# atmega.net
KiCad netlist of a schematic drawn in EAGLE
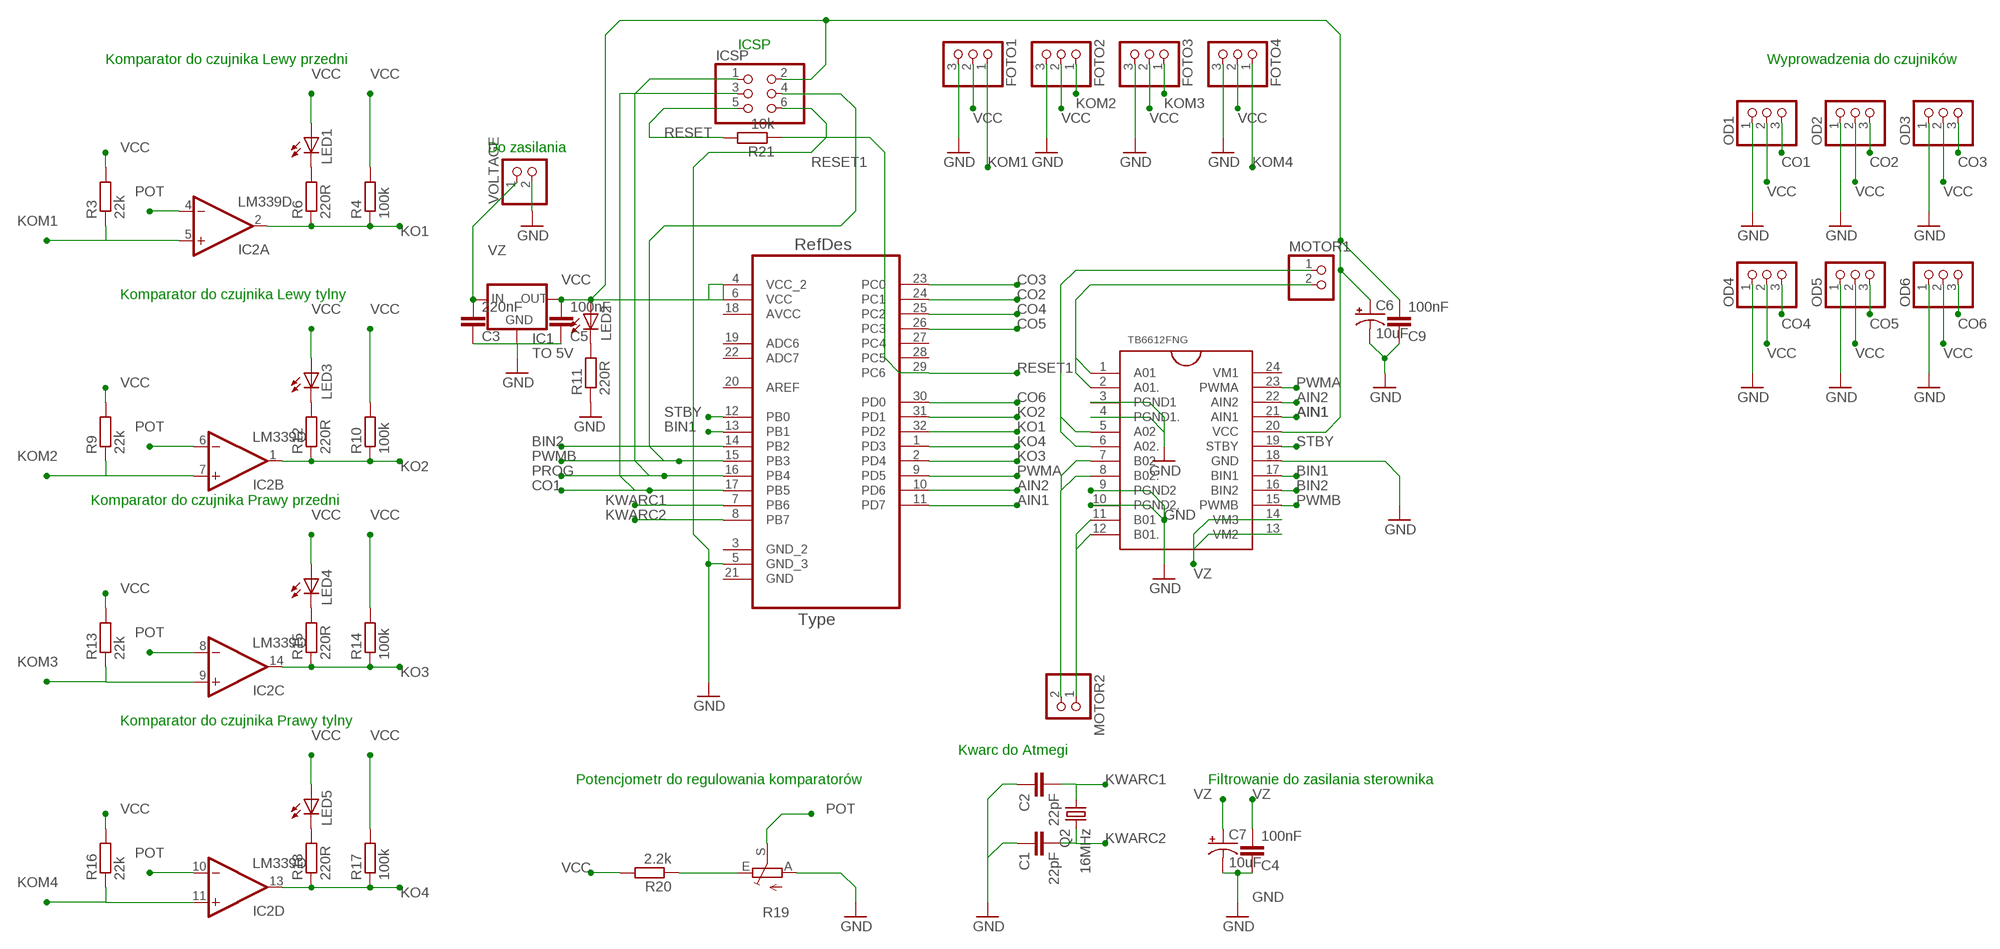
[diagram p0: schematic, sheet 1]

(export (version "E")
  (design (tool "Eeschema 10.0.6"))
  (components
    (comp (ref "C1")
      (value "22pF")
      (footprint "eagle-import:C0805")
      (fields (field (name "SPICEPREFIX") "C"))
      (libsource (lib "eagle-import") (part "C-EUC0805"))
    )
    (comp (ref "C2")
      (value "22pF")
      (footprint "eagle-import:C0805")
      (libsource (lib "eagle-import") (part "C-EUC0805"))
    )
    (comp (ref "C3")
      (value "220nF")
      (footprint "eagle-import:C0805")
      (fields (field (name "SPICEPREFIX") "C"))
      (libsource (lib "eagle-import") (part "C-EUC0805"))
    )
    (comp (ref "C4")
      (value "100nF")
      (footprint "eagle-import:C0805")
      (fields (field (name "SPICEPREFIX") "C"))
      (libsource (lib "eagle-import") (part "C-EUC0805"))
    )
    (comp (ref "C5")
      (value "100nF")
      (footprint "eagle-import:C0805")
      (fields (field (name "SPICEPREFIX") "C"))
      (libsource (lib "eagle-import") (part "C-EUC0805"))
    )
    (comp (ref "C6")
      (value "10uF")
      (footprint "eagle-import:PANASONIC_C")
      (libsource (lib "eagle-import") (part "22UF-POLAR-PANASONIC_C-35V-20%"))
    )
    (comp (ref "C7")
      (value "10uF")
      (footprint "eagle-import:PANASONIC_C")
      (libsource (lib "eagle-import") (part "22UF-POLAR-PANASONIC_C-35V-20%"))
    )
    (comp (ref "C9")
      (value "100nF")
      (footprint "eagle-import:C0805")
      (fields (field (name "SPICEPREFIX") "C"))
      (libsource (lib "eagle-import") (part "C-EUC0805"))
    )
    (comp (ref "FOTO1")
      (value "PINHD-1X3")
      (footprint "eagle-import:1X03")
      (libsource (lib "eagle-import") (part "PINHD-1X3"))
    )
    (comp (ref "FOTO2")
      (value "PINHD-1X3")
      (footprint "eagle-import:1X03")
      (libsource (lib "eagle-import") (part "PINHD-1X3"))
    )
    (comp (ref "FOTO3")
      (value "PINHD-1X3")
      (footprint "eagle-import:1X03")
      (libsource (lib "eagle-import") (part "PINHD-1X3"))
    )
    (comp (ref "FOTO4")
      (value "PINHD-1X3")
      (footprint "eagle-import:1X03")
      (libsource (lib "eagle-import") (part "PINHD-1X3"))
    )
    (comp (ref "IC1")
      (value "TO 5V")
      (footprint "eagle-import:TO220V")
      (libsource (lib "eagle-import") (part "LM1117T--V5.0"))
    )
    (comp (ref "IC2")
      (value "LM339D")
      (footprint "eagle-import:SO14")
      (libsource (lib "eagle-import") (part "LM339D"))
    )
    (comp (ref "ICSP")
      (value "PINHD-2X3")
      (footprint "eagle-import:2X03")
      (libsource (lib "eagle-import") (part "PINHD-2X3"))
    )
    (comp (ref "LED1")
      (value "LEDCHIPLED_0805")
      (footprint "eagle-import:CHIPLED_0805")
      (libsource (lib "eagle-import") (part "LEDCHIPLED_0805"))
    )
    (comp (ref "LED2")
      (value "LEDCHIPLED_0805")
      (footprint "eagle-import:CHIPLED_0805")
      (libsource (lib "eagle-import") (part "LEDCHIPLED_0805"))
    )
    (comp (ref "LED3")
      (value "LEDCHIPLED_0805")
      (footprint "eagle-import:CHIPLED_0805")
      (libsource (lib "eagle-import") (part "LEDCHIPLED_0805"))
    )
    (comp (ref "LED4")
      (value "LEDCHIPLED_0805")
      (footprint "eagle-import:CHIPLED_0805")
      (libsource (lib "eagle-import") (part "LEDCHIPLED_0805"))
    )
    (comp (ref "LED5")
      (value "LEDCHIPLED_0805")
      (footprint "eagle-import:CHIPLED_0805")
      (libsource (lib "eagle-import") (part "LEDCHIPLED_0805"))
    )
    (comp (ref "MOTOR1")
      (value "PINHD-1X2")
      (footprint "eagle-import:1X02")
      (libsource (lib "eagle-import") (part "PINHD-1X2"))
    )
    (comp (ref "MOTOR2")
      (value "PINHD-1X2")
      (footprint "eagle-import:1X02")
      (libsource (lib "eagle-import") (part "PINHD-1X2"))
    )
    (comp (ref "OD1")
      (value "PINHD-1X3")
      (footprint "eagle-import:1X03")
      (libsource (lib "eagle-import") (part "PINHD-1X3"))
    )
    (comp (ref "OD2")
      (value "PINHD-1X3")
      (footprint "eagle-import:1X03")
      (libsource (lib "eagle-import") (part "PINHD-1X3"))
    )
    (comp (ref "OD3")
      (value "PINHD-1X3")
      (footprint "eagle-import:1X03")
      (libsource (lib "eagle-import") (part "PINHD-1X3"))
    )
    (comp (ref "OD4")
      (value "PINHD-1X3")
      (footprint "eagle-import:1X03")
      (libsource (lib "eagle-import") (part "PINHD-1X3"))
    )
    (comp (ref "OD5")
      (value "PINHD-1X3")
      (footprint "eagle-import:1X03")
      (libsource (lib "eagle-import") (part "PINHD-1X3"))
    )
    (comp (ref "OD6")
      (value "PINHD-1X3")
      (footprint "eagle-import:1X03")
      (libsource (lib "eagle-import") (part "PINHD-1X3"))
    )
    (comp (ref "Q2")
      (value "16MHz")
      (footprint "eagle-import:CSM-7X-DU")
      (libsource (lib "eagle-import") (part "CSM-7X-DU"))
    )
    (comp (ref "R3")
      (value "22k")
      (footprint "eagle-import:M0805")
      (libsource (lib "eagle-import") (part "R-EU_M0805"))
    )
    (comp (ref "R4")
      (value "100k")
      (footprint "eagle-import:M0805")
      (libsource (lib "eagle-import") (part "R-EU_M0805"))
    )
    (comp (ref "R6")
      (value "220R")
      (footprint "eagle-import:M0805")
      (libsource (lib "eagle-import") (part "R-EU_M0805"))
    )
    (comp (ref "R9")
      (value "22k")
      (footprint "eagle-import:M0805")
      (libsource (lib "eagle-import") (part "R-EU_M0805"))
    )
    (comp (ref "R10")
      (value "100k")
      (footprint "eagle-import:M0805")
      (libsource (lib "eagle-import") (part "R-EU_M0805"))
    )
    (comp (ref "R11")
      (value "220R")
      (footprint "eagle-import:M0805")
      (libsource (lib "eagle-import") (part "R-EU_M0805"))
    )
    (comp (ref "R12")
      (value "220R")
      (footprint "eagle-import:M0805")
      (libsource (lib "eagle-import") (part "R-EU_M0805"))
    )
    (comp (ref "R13")
      (value "22k")
      (footprint "eagle-import:M0805")
      (libsource (lib "eagle-import") (part "R-EU_M0805"))
    )
    (comp (ref "R14")
      (value "100k")
      (footprint "eagle-import:M0805")
      (libsource (lib "eagle-import") (part "R-EU_M0805"))
    )
    (comp (ref "R15")
      (value "220R")
      (footprint "eagle-import:M0805")
      (libsource (lib "eagle-import") (part "R-EU_M0805"))
    )
    (comp (ref "R16")
      (value "22k")
      (footprint "eagle-import:M0805")
      (libsource (lib "eagle-import") (part "R-EU_M0805"))
    )
    (comp (ref "R17")
      (value "100k")
      (footprint "eagle-import:M0805")
      (libsource (lib "eagle-import") (part "R-EU_M0805"))
    )
    (comp (ref "R18")
      (value "220R")
      (footprint "eagle-import:M0805")
      (libsource (lib "eagle-import") (part "R-EU_M0805"))
    )
    (comp (ref "R19")
      (value "TRIM_EU-B25P")
      (footprint "eagle-import:B25P")
      (libsource (lib "eagle-import") (part "TRIM_EU-B25P"))
    )
    (comp (ref "R20")
      (value "2.2k")
      (footprint "eagle-import:M0805")
      (libsource (lib "eagle-import") (part "R-EU_M0805"))
    )
    (comp (ref "R21")
      (value "10k")
      (footprint "eagle-import:M0805")
      (libsource (lib "eagle-import") (part "R-EU_M0805"))
    )
    (comp (ref "U$1")
      (value "TB6612FNG")
      (footprint "eagle-import:SSOP24")
      (libsource (lib "eagle-import") (part "TB6612FNG"))
    )
    (comp (ref "U1")
      (value "ATMEGA328P-AU")
      (footprint "eagle-import:QFP80P900X900X120-32N")
      (libsource (lib "eagle-import") (part "ATMEGA328P-AU"))
    )
    (comp (ref "VOLTAGE")
      (value "PINHD-1X2")
      (footprint "eagle-import:1X02")
      (libsource (lib "eagle-import") (part "PINHD-1X2"))
    )
  )
  (nets
    (net (code "1") (name "/AIN1") (class "Default")
      (node (ref "U$1") (pin "21") (pinfunction "AIN1_21") (pintype "bidirectional"))
      (node (ref "U1") (pin "11") (pinfunction "PD7_11") (pintype "bidirectional"))
    )
    (net (code "2") (name "/AIN2") (class "Default")
      (node (ref "U$1") (pin "22") (pinfunction "AIN2_22") (pintype "bidirectional"))
      (node (ref "U1") (pin "10") (pinfunction "PD6_10") (pintype "bidirectional"))
    )
    (net (code "3") (name "/AVCC") (class "Default")
      (node (ref "U1") (pin "18") (pinfunction "AVCC_18") (pintype "power_in"))
    )
    (net (code "4") (name "/BIN1") (class "Default")
      (node (ref "U$1") (pin "17") (pinfunction "BIN1_17") (pintype "bidirectional"))
      (node (ref "U1") (pin "13") (pinfunction "PB1_13") (pintype "bidirectional"))
    )
    (net (code "5") (name "/BIN2") (class "Default")
      (node (ref "U$1") (pin "16") (pinfunction "BIN2_16") (pintype "bidirectional"))
      (node (ref "U1") (pin "14") (pinfunction "PB2_14") (pintype "bidirectional"))
    )
    (net (code "6") (name "/CO1") (class "Default")
      (node (ref "ICSP") (pin "3") (pinfunction "3_3") (pintype "passive"))
      (node (ref "OD1") (pin "3") (pinfunction "3_3") (pintype "passive"))
      (node (ref "U1") (pin "17") (pinfunction "PB5_17") (pintype "bidirectional"))
    )
    (net (code "7") (name "/CO2") (class "Default")
      (node (ref "OD2") (pin "3") (pinfunction "3_3") (pintype "passive"))
      (node (ref "U1") (pin "24") (pinfunction "PC1_24") (pintype "bidirectional"))
    )
    (net (code "8") (name "/CO3") (class "Default")
      (node (ref "OD3") (pin "3") (pinfunction "3_3") (pintype "passive"))
      (node (ref "U1") (pin "23") (pinfunction "PC0_23") (pintype "bidirectional"))
    )
    (net (code "9") (name "/CO4") (class "Default")
      (node (ref "OD4") (pin "3") (pinfunction "3_3") (pintype "passive"))
      (node (ref "U1") (pin "25") (pinfunction "PC2_25") (pintype "bidirectional"))
    )
    (net (code "10") (name "/CO5") (class "Default")
      (node (ref "OD5") (pin "3") (pinfunction "3_3") (pintype "passive"))
      (node (ref "U1") (pin "26") (pinfunction "PC3_26") (pintype "bidirectional"))
    )
    (net (code "11") (name "/CO6") (class "Default")
      (node (ref "OD6") (pin "3") (pinfunction "3_3") (pintype "passive"))
      (node (ref "U1") (pin "30") (pinfunction "PD0_30") (pintype "bidirectional"))
    )
    (net (code "12") (name "/KO1") (class "Default")
      (node (ref "IC2") (pin "2") (pinfunction "OUT_2") (pintype "open_collector"))
      (node (ref "R4") (pin "1") (pinfunction "1_1") (pintype "passive"))
      (node (ref "R6") (pin "1") (pinfunction "1_1") (pintype "passive"))
      (node (ref "U1") (pin "32") (pinfunction "PD2_32") (pintype "bidirectional"))
    )
    (net (code "13") (name "/KO2") (class "Default")
      (node (ref "IC2") (pin "1") (pinfunction "OUT_1") (pintype "open_collector"))
      (node (ref "R10") (pin "1") (pinfunction "1_1") (pintype "passive"))
      (node (ref "R12") (pin "1") (pinfunction "1_1") (pintype "passive"))
      (node (ref "U1") (pin "31") (pinfunction "PD1_31") (pintype "bidirectional"))
    )
    (net (code "14") (name "/KO3") (class "Default")
      (node (ref "IC2") (pin "14") (pinfunction "OUT_14") (pintype "open_collector"))
      (node (ref "R14") (pin "1") (pinfunction "1_1") (pintype "passive"))
      (node (ref "R15") (pin "1") (pinfunction "1_1") (pintype "passive"))
      (node (ref "U1") (pin "2") (pinfunction "PD4_2") (pintype "bidirectional"))
    )
    (net (code "15") (name "/KO4") (class "Default")
      (node (ref "IC2") (pin "13") (pinfunction "OUT_13") (pintype "open_collector"))
      (node (ref "R17") (pin "1") (pinfunction "1_1") (pintype "passive"))
      (node (ref "R18") (pin "1") (pinfunction "1_1") (pintype "passive"))
      (node (ref "U1") (pin "1") (pinfunction "PD3_1") (pintype "bidirectional"))
    )
    (net (code "16") (name "/KOM1") (class "Default")
      (node (ref "FOTO1") (pin "1") (pinfunction "1_1") (pintype "passive"))
      (node (ref "IC2") (pin "5") (pinfunction "+IN_5") (pintype "input"))
      (node (ref "R3") (pin "1") (pinfunction "1_1") (pintype "passive"))
    )
    (net (code "17") (name "/KOM2") (class "Default")
      (node (ref "FOTO2") (pin "1") (pinfunction "1_1") (pintype "passive"))
      (node (ref "IC2") (pin "7") (pinfunction "+IN_7") (pintype "input"))
      (node (ref "R9") (pin "1") (pinfunction "1_1") (pintype "passive"))
    )
    (net (code "18") (name "/KOM3") (class "Default")
      (node (ref "FOTO3") (pin "1") (pinfunction "1_1") (pintype "passive"))
      (node (ref "IC2") (pin "9") (pinfunction "+IN_9") (pintype "input"))
      (node (ref "R13") (pin "1") (pinfunction "1_1") (pintype "passive"))
    )
    (net (code "19") (name "/KOM4") (class "Default")
      (node (ref "FOTO4") (pin "1") (pinfunction "1_1") (pintype "passive"))
      (node (ref "IC2") (pin "11") (pinfunction "+IN_11") (pintype "input"))
      (node (ref "R16") (pin "1") (pinfunction "1_1") (pintype "passive"))
    )
    (net (code "20") (name "/KWARC1") (class "Default")
      (node (ref "C2") (pin "2") (pinfunction "2_2") (pintype "passive"))
      (node (ref "Q2") (pin "1") (pinfunction "1_1") (pintype "passive"))
      (node (ref "U1") (pin "7") (pinfunction "PB6_7") (pintype "bidirectional"))
    )
    (net (code "21") (name "/KWARC2") (class "Default")
      (node (ref "C1") (pin "2") (pinfunction "2_2") (pintype "passive"))
      (node (ref "Q2") (pin "2") (pinfunction "2_2") (pintype "passive"))
      (node (ref "U1") (pin "8") (pinfunction "PB7_8") (pintype "bidirectional"))
    )
    (net (code "22") (name "/POT") (class "Default")
      (node (ref "IC2") (pin "10") (pinfunction "-IN_10") (pintype "input"))
      (node (ref "IC2") (pin "4") (pinfunction "-IN_4") (pintype "input"))
      (node (ref "IC2") (pin "6") (pinfunction "-IN_6") (pintype "input"))
      (node (ref "IC2") (pin "8") (pinfunction "-IN_8") (pintype "input"))
      (node (ref "R19") (pin "S") (pinfunction "S_S") (pintype "passive"))
    )
    (net (code "23") (name "/PROG") (class "Default")
      (node (ref "ICSP") (pin "1") (pinfunction "1_1") (pintype "passive"))
      (node (ref "U1") (pin "16") (pinfunction "PB4_16") (pintype "bidirectional"))
    )
    (net (code "24") (name "/PWMA") (class "Default")
      (node (ref "U$1") (pin "23") (pinfunction "PWMA_23") (pintype "bidirectional"))
      (node (ref "U1") (pin "9") (pinfunction "PD5_9") (pintype "bidirectional"))
    )
    (net (code "25") (name "/PWMB") (class "Default")
      (node (ref "ICSP") (pin "4") (pinfunction "4_4") (pintype "passive"))
      (node (ref "U$1") (pin "15") (pinfunction "PWMB_15") (pintype "bidirectional"))
      (node (ref "U1") (pin "15") (pinfunction "PB3_15") (pintype "bidirectional"))
    )
    (net (code "26") (name "/RESET") (class "Default")
      (node (ref "ICSP") (pin "5") (pinfunction "5_5") (pintype "passive"))
      (node (ref "R21") (pin "2") (pinfunction "2_2") (pintype "passive"))
    )
    (net (code "27") (name "/RESET1") (class "Default")
      (node (ref "R21") (pin "1") (pinfunction "1_1") (pintype "passive"))
      (node (ref "U1") (pin "29") (pinfunction "PC6_29") (pintype "bidirectional"))
    )
    (net (code "28") (name "/STBY") (class "Default")
      (node (ref "U$1") (pin "19") (pinfunction "STBY_19") (pintype "bidirectional"))
      (node (ref "U1") (pin "12") (pinfunction "PB0_12") (pintype "bidirectional"))
    )
    (net (code "29") (name "/VCC") (class "Default")
      (node (ref "C5") (pin "2") (pinfunction "2_2") (pintype "passive"))
      (node (ref "C6") (pin "+") (pinfunction "+_+") (pintype "passive"))
      (node (ref "C9") (pin "2") (pinfunction "2_2") (pintype "passive"))
      (node (ref "FOTO1") (pin "2") (pinfunction "2_2") (pintype "passive"))
      (node (ref "FOTO2") (pin "2") (pinfunction "2_2") (pintype "passive"))
      (node (ref "FOTO3") (pin "2") (pinfunction "2_2") (pintype "passive"))
      (node (ref "FOTO4") (pin "2") (pinfunction "2_2") (pintype "passive"))
      (node (ref "IC1") (pin "2") (pinfunction "OUT_2") (pintype "passive"))
      (node (ref "ICSP") (pin "2") (pinfunction "2_2") (pintype "passive"))
      (node (ref "LED1") (pin "A") (pinfunction "A_A") (pintype "passive"))
      (node (ref "LED2") (pin "A") (pinfunction "A_A") (pintype "passive"))
      (node (ref "LED3") (pin "A") (pinfunction "A_A") (pintype "passive"))
      (node (ref "LED4") (pin "A") (pinfunction "A_A") (pintype "passive"))
      (node (ref "LED5") (pin "A") (pinfunction "A_A") (pintype "passive"))
      (node (ref "OD1") (pin "2") (pinfunction "2_2") (pintype "passive"))
      (node (ref "OD2") (pin "2") (pinfunction "2_2") (pintype "passive"))
      (node (ref "OD3") (pin "2") (pinfunction "2_2") (pintype "passive"))
      (node (ref "OD4") (pin "2") (pinfunction "2_2") (pintype "passive"))
      (node (ref "OD5") (pin "2") (pinfunction "2_2") (pintype "passive"))
      (node (ref "OD6") (pin "2") (pinfunction "2_2") (pintype "passive"))
      (node (ref "R10") (pin "2") (pinfunction "2_2") (pintype "passive"))
      (node (ref "R13") (pin "2") (pinfunction "2_2") (pintype "passive"))
      (node (ref "R14") (pin "2") (pinfunction "2_2") (pintype "passive"))
      (node (ref "R16") (pin "2") (pinfunction "2_2") (pintype "passive"))
      (node (ref "R17") (pin "2") (pinfunction "2_2") (pintype "passive"))
      (node (ref "R20") (pin "2") (pinfunction "2_2") (pintype "passive"))
      (node (ref "R3") (pin "2") (pinfunction "2_2") (pintype "passive"))
      (node (ref "R4") (pin "2") (pinfunction "2_2") (pintype "passive"))
      (node (ref "R9") (pin "2") (pinfunction "2_2") (pintype "passive"))
      (node (ref "U$1") (pin "20") (pinfunction "VCC_20") (pintype "bidirectional"))
      (node (ref "U1") (pin "4") (pinfunction "VCC_2_4") (pintype "power_in"))
      (node (ref "U1") (pin "6") (pinfunction "VCC_6") (pintype "power_in"))
    )
    (net (code "30") (name "/VZ") (class "Default")
      (node (ref "C3") (pin "2") (pinfunction "2_2") (pintype "passive"))
      (node (ref "C4") (pin "2") (pinfunction "2_2") (pintype "passive"))
      (node (ref "C7") (pin "+") (pinfunction "+_+") (pintype "passive"))
      (node (ref "IC1") (pin "3") (pinfunction "IN_3") (pintype "input"))
      (node (ref "U$1") (pin "13") (pinfunction "VM2_13") (pintype "bidirectional"))
      (node (ref "U$1") (pin "14") (pinfunction "VM3_14") (pintype "bidirectional"))
      (node (ref "VOLTAGE") (pin "1") (pinfunction "1_1") (pintype "passive"))
    )
    (net (code "31") (name "GND") (class "Default")
      (node (ref "C1") (pin "1") (pinfunction "1_1") (pintype "passive"))
      (node (ref "C2") (pin "1") (pinfunction "1_1") (pintype "passive"))
      (node (ref "C3") (pin "1") (pinfunction "1_1") (pintype "passive"))
      (node (ref "C4") (pin "1") (pinfunction "1_1") (pintype "passive"))
      (node (ref "C5") (pin "1") (pinfunction "1_1") (pintype "passive"))
      (node (ref "C6") (pin "-") (pinfunction "-_-") (pintype "passive"))
      (node (ref "C7") (pin "-") (pinfunction "-_-") (pintype "passive"))
      (node (ref "C9") (pin "1") (pinfunction "1_1") (pintype "passive"))
      (node (ref "FOTO1") (pin "3") (pinfunction "3_3") (pintype "passive"))
      (node (ref "FOTO2") (pin "3") (pinfunction "3_3") (pintype "passive"))
      (node (ref "FOTO3") (pin "3") (pinfunction "3_3") (pintype "passive"))
      (node (ref "FOTO4") (pin "3") (pinfunction "3_3") (pintype "passive"))
      (node (ref "IC1") (pin "1") (pinfunction "GND_1") (pintype "input"))
      (node (ref "ICSP") (pin "6") (pinfunction "6_6") (pintype "passive"))
      (node (ref "OD1") (pin "1") (pinfunction "1_1") (pintype "passive"))
      (node (ref "OD2") (pin "1") (pinfunction "1_1") (pintype "passive"))
      (node (ref "OD3") (pin "1") (pinfunction "1_1") (pintype "passive"))
      (node (ref "OD4") (pin "1") (pinfunction "1_1") (pintype "passive"))
      (node (ref "OD5") (pin "1") (pinfunction "1_1") (pintype "passive"))
      (node (ref "OD6") (pin "1") (pinfunction "1_1") (pintype "passive"))
      (node (ref "R11") (pin "1") (pinfunction "1_1") (pintype "passive"))
      (node (ref "R19") (pin "A") (pinfunction "A_A") (pintype "passive"))
      (node (ref "U$1") (pin "10") (pinfunction "PGND2._10") (pintype "bidirectional"))
      (node (ref "U$1") (pin "18") (pinfunction "GND_18") (pintype "bidirectional"))
      (node (ref "U$1") (pin "3") (pinfunction "PGND1_3") (pintype "bidirectional"))
      (node (ref "U$1") (pin "4") (pinfunction "PGND1._4") (pintype "bidirectional"))
      (node (ref "U$1") (pin "9") (pinfunction "PGND2_9") (pintype "bidirectional"))
      (node (ref "U1") (pin "5") (pinfunction "GND_3_5") (pintype "passive"))
      (node (ref "VOLTAGE") (pin "2") (pinfunction "2_2") (pintype "passive"))
    )
    (net (code "32") (name "Net-(LED1-PadC)") (class "Default")
      (node (ref "LED1") (pin "C") (pinfunction "C_C") (pintype "passive"))
      (node (ref "R6") (pin "2") (pinfunction "2_2") (pintype "passive"))
    )
    (net (code "33") (name "Net-(LED2-PadC)") (class "Default")
      (node (ref "LED2") (pin "C") (pinfunction "C_C") (pintype "passive"))
      (node (ref "R11") (pin "2") (pinfunction "2_2") (pintype "passive"))
    )
    (net (code "34") (name "Net-(LED3-PadC)") (class "Default")
      (node (ref "LED3") (pin "C") (pinfunction "C_C") (pintype "passive"))
      (node (ref "R12") (pin "2") (pinfunction "2_2") (pintype "passive"))
    )
    (net (code "35") (name "Net-(LED4-PadC)") (class "Default")
      (node (ref "LED4") (pin "C") (pinfunction "C_C") (pintype "passive"))
      (node (ref "R15") (pin "2") (pinfunction "2_2") (pintype "passive"))
    )
    (net (code "36") (name "Net-(LED5-PadC)") (class "Default")
      (node (ref "LED5") (pin "C") (pinfunction "C_C") (pintype "passive"))
      (node (ref "R18") (pin "2") (pinfunction "2_2") (pintype "passive"))
    )
    (net (code "37") (name "Net-(R19-PadE)") (class "Default")
      (node (ref "R19") (pin "E") (pinfunction "E_E") (pintype "passive"))
      (node (ref "R20") (pin "1") (pinfunction "1_1") (pintype "passive"))
    )
    (net (code "38") (name "Net-(U$1-A01)") (class "Default")
      (node (ref "MOTOR1") (pin "2") (pinfunction "2_2") (pintype "passive"))
      (node (ref "U$1") (pin "1") (pinfunction "A01_1") (pintype "bidirectional"))
      (node (ref "U$1") (pin "2") (pinfunction "A01._2") (pintype "bidirectional"))
    )
    (net (code "39") (name "Net-(U$1-A02)") (class "Default")
      (node (ref "MOTOR1") (pin "1") (pinfunction "1_1") (pintype "passive"))
      (node (ref "U$1") (pin "5") (pinfunction "A02_5") (pintype "bidirectional"))
      (node (ref "U$1") (pin "6") (pinfunction "A02._6") (pintype "bidirectional"))
    )
    (net (code "40") (name "Net-(U$1-B01)") (class "Default")
      (node (ref "MOTOR2") (pin "1") (pinfunction "1_1") (pintype "passive"))
      (node (ref "U$1") (pin "11") (pinfunction "B01_11") (pintype "bidirectional"))
      (node (ref "U$1") (pin "12") (pinfunction "B01._12") (pintype "bidirectional"))
    )
    (net (code "41") (name "Net-(U$1-B02)") (class "Default")
      (node (ref "MOTOR2") (pin "2") (pinfunction "2_2") (pintype "passive"))
      (node (ref "U$1") (pin "7") (pinfunction "B02_7") (pintype "bidirectional"))
      (node (ref "U$1") (pin "8") (pinfunction "B02._8") (pintype "bidirectional"))
    )
    (net (code "42") (name "unconnected-(U$1-VM1-Pad24)") (class "Default")
      (node (ref "U$1") (pin "24") (pinfunction "VM1_24") (pintype "bidirectional"))
    )
    (net (code "43") (name "unconnected-(U1-ADC6-Pad19)") (class "Default")
      (node (ref "U1") (pin "19") (pinfunction "ADC6_19") (pintype "input"))
    )
    (net (code "44") (name "unconnected-(U1-ADC7-Pad22)") (class "Default")
      (node (ref "U1") (pin "22") (pinfunction "ADC7_22") (pintype "input"))
    )
    (net (code "45") (name "unconnected-(U1-AREF-Pad20)") (class "Default")
      (node (ref "U1") (pin "20") (pinfunction "AREF_20") (pintype "input"))
    )
    (net (code "46") (name "unconnected-(U1-GND-Pad21)") (class "Default")
      (node (ref "U1") (pin "21") (pinfunction "GND_21") (pintype "passive"))
    )
    (net (code "47") (name "unconnected-(U1-GND_2-Pad3)") (class "Default")
      (node (ref "U1") (pin "3") (pinfunction "GND_2_3") (pintype "passive"))
    )
    (net (code "48") (name "unconnected-(U1-PC4-Pad27)") (class "Default")
      (node (ref "U1") (pin "27") (pinfunction "PC4_27") (pintype "bidirectional"))
    )
    (net (code "49") (name "unconnected-(U1-PC5-Pad28)") (class "Default")
      (node (ref "U1") (pin "28") (pinfunction "PC5_28") (pintype "bidirectional"))
    )
  )
)
